# ir-sensor-breakout.net
KiCad netlist of a schematic drawn in EAGLE
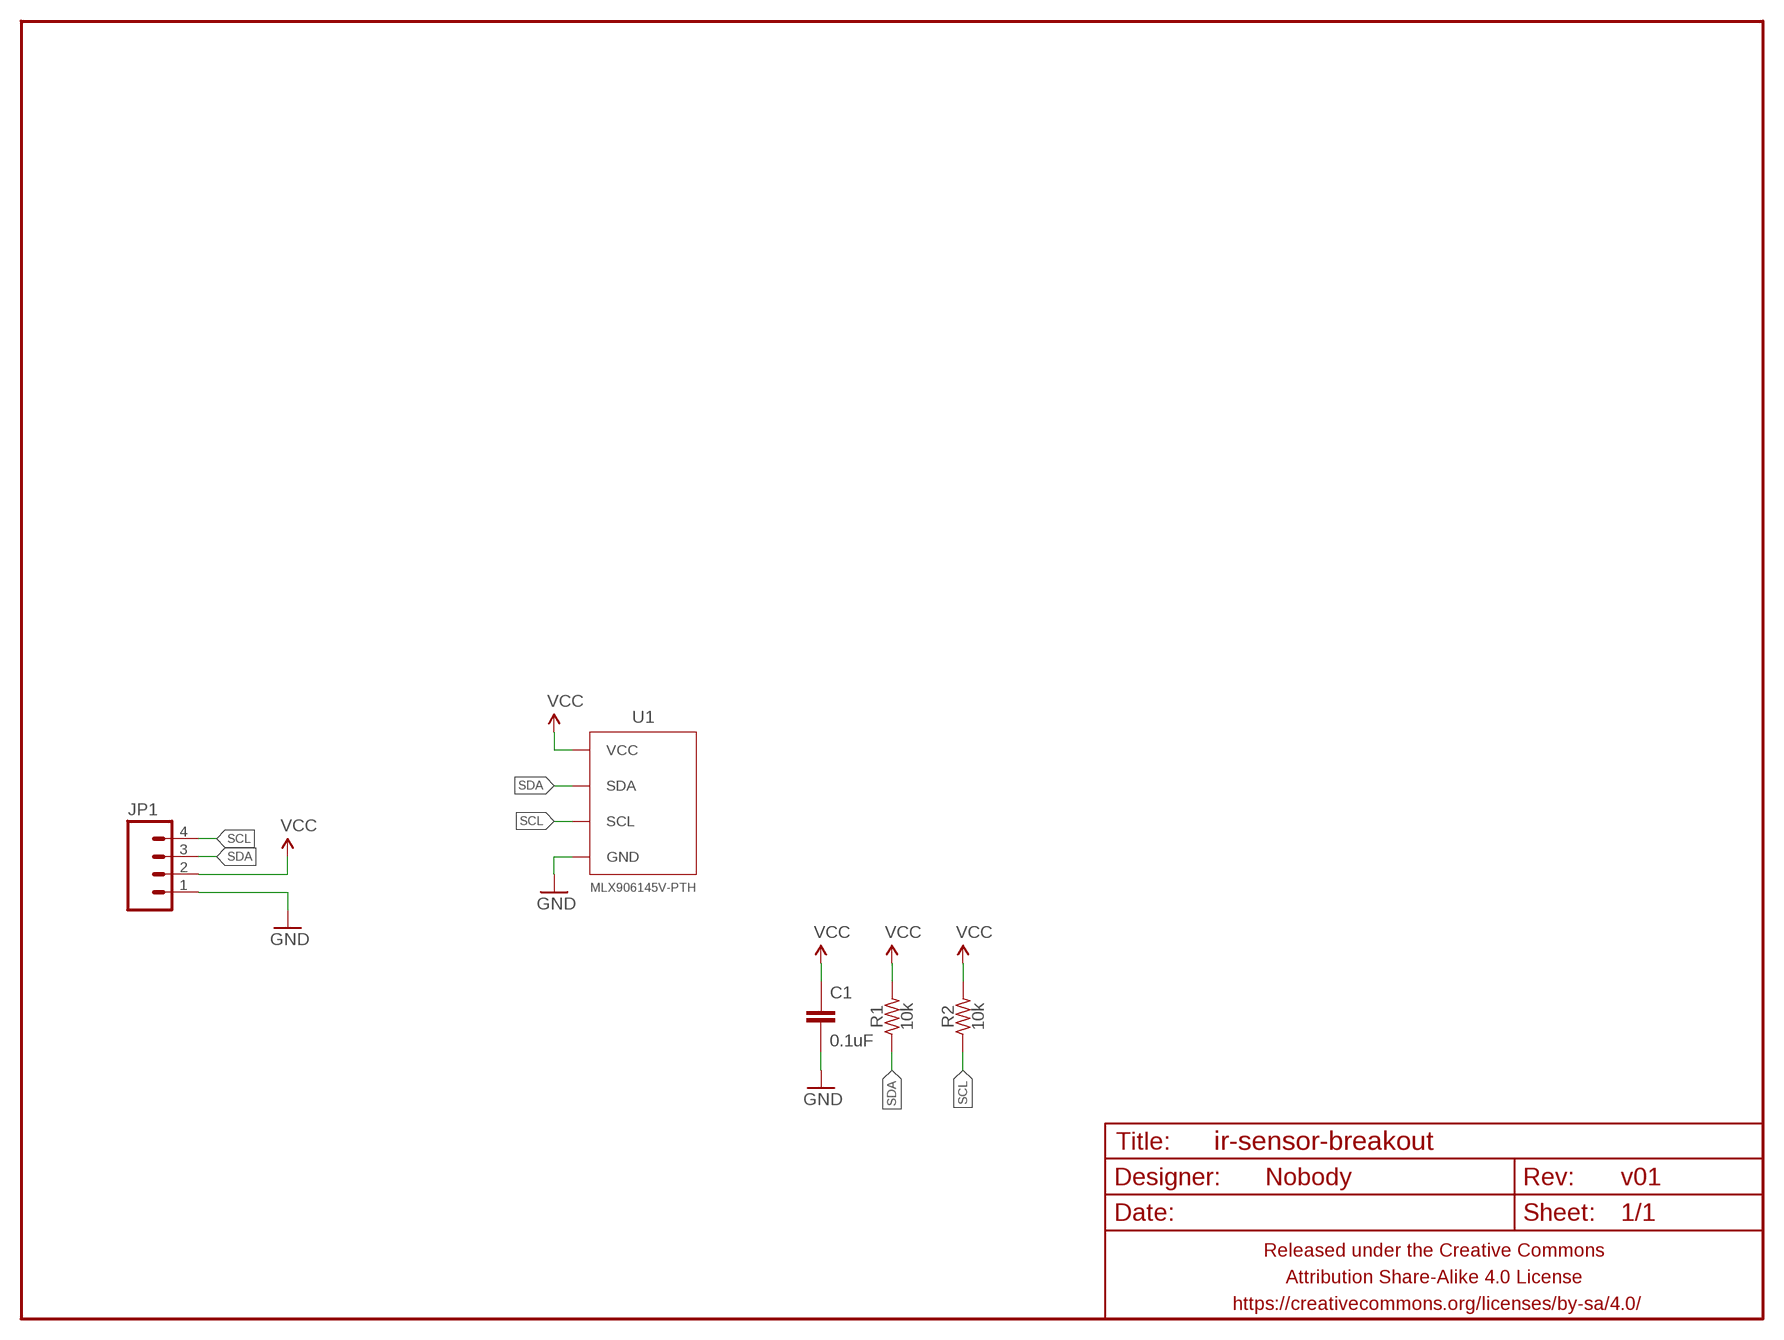
[diagram p0: schematic, sheet 1]

(export (version "E")
  (design (tool "Eeschema 10.0.6"))
  (components
    (comp (ref "C1")
      (value "0.1uF")
      (footprint "eagle-import:C025-024X044")
      (libsource (lib "eagle-import") (part "CAPACITOR-CERAMIC025-024X044"))
    )
    (comp (ref "FRAME1")
      (value "FRAME-LETTERNO_PACKAGE")
      (footprint "eagle-import:DUMMY")
      (fields (field (name "DESIGNER") "Nobody"))
      (libsource (lib "eagle-import") (part "FRAME-LETTERNO_PACKAGE"))
    )
    (comp (ref "JP1")
      (value "M04JST-PTH")
      (footprint "eagle-import:JST-4-PH-RA-PTH")
      (libsource (lib "eagle-import") (part "M04JST-PTH"))
    )
    (comp (ref "R1")
      (value "10k")
      (footprint "eagle-import:RESISTOR-AXIAL-PTH-7.62MM")
      (libsource (lib "eagle-import") (part "RESISTORPTH-AXIAL-7.62MM"))
    )
    (comp (ref "R2")
      (value "10k")
      (footprint "eagle-import:RESISTOR-AXIAL-PTH-7.62MM")
      (libsource (lib "eagle-import") (part "RESISTORPTH-AXIAL-7.62MM"))
    )
    (comp (ref "U1")
      (value "MLX906145V-PTH")
      (footprint "eagle-import:TO-39-4")
      (libsource (lib "eagle-import") (part "MLX906145V-PTH"))
    )
  )
  (nets
    (net (code "1") (name "GND") (class "Default")
      (node (ref "C1") (pin "2") (pinfunction "2_2") (pintype "passive"))
      (node (ref "JP1") (pin "1") (pinfunction "1_1") (pintype "passive"))
      (node (ref "U1") (pin "4") (pinfunction "GND_4") (pintype "bidirectional"))
    )
    (net (code "2") (name "SCL") (class "Default")
      (node (ref "JP1") (pin "4") (pinfunction "4_4") (pintype "passive"))
      (node (ref "R2") (pin "P$1") (pinfunction "1_P$1") (pintype "passive"))
      (node (ref "U1") (pin "1") (pinfunction "SCL_1") (pintype "bidirectional"))
    )
    (net (code "3") (name "SDA") (class "Default")
      (node (ref "JP1") (pin "3") (pinfunction "3_3") (pintype "passive"))
      (node (ref "R1") (pin "P$1") (pinfunction "1_P$1") (pintype "passive"))
      (node (ref "U1") (pin "2") (pinfunction "SDA_2") (pintype "bidirectional"))
    )
    (net (code "4") (name "VCC") (class "Default")
      (node (ref "C1") (pin "1") (pinfunction "1_1") (pintype "passive"))
      (node (ref "JP1") (pin "2") (pinfunction "2_2") (pintype "passive"))
      (node (ref "R1") (pin "P$2") (pinfunction "2_P$2") (pintype "passive"))
      (node (ref "R2") (pin "P$2") (pinfunction "2_P$2") (pintype "passive"))
      (node (ref "U1") (pin "3") (pinfunction "VCC_3") (pintype "bidirectional"))
    )
  )
)
